# stereo-amp-rev1.net
KiCad netlist of a schematic drawn in EAGLE
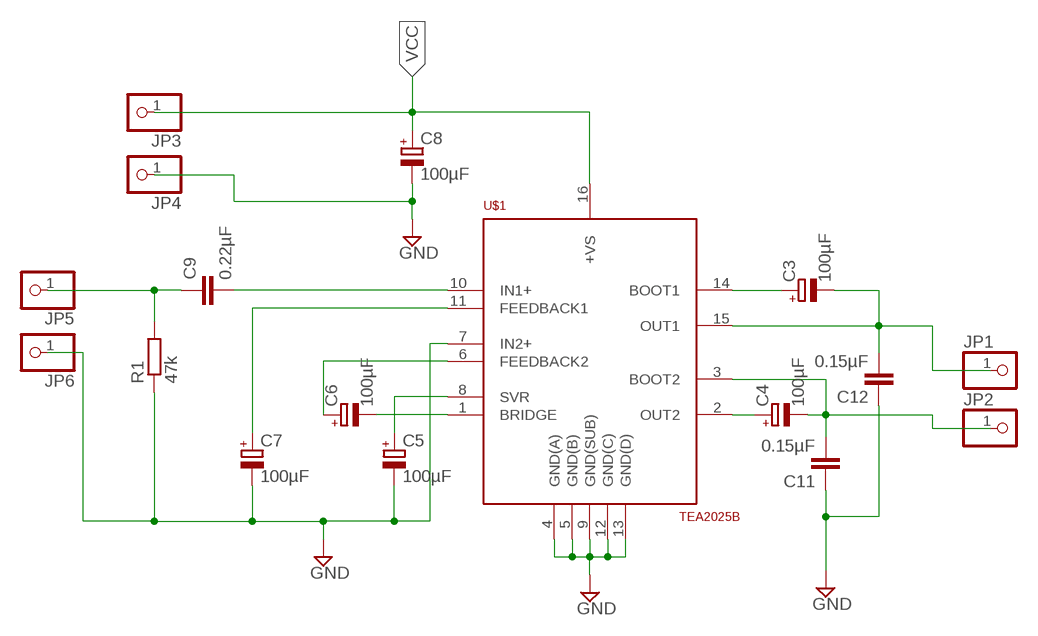
[diagram p0: schematic, sheet 1]

(export (version "E")
  (design (tool "Eeschema 10.0.6"))
  (components
    (comp (ref "C3")
      (value "100µF")
      (footprint "eagle-import:E2,5-7")
      (libsource (lib "eagle-import") (part "CPOL-EUE2.5-7"))
    )
    (comp (ref "C4")
      (value "100µF")
      (footprint "eagle-import:E2,5-7")
      (libsource (lib "eagle-import") (part "CPOL-EUE2.5-7"))
    )
    (comp (ref "C5")
      (value "100µF")
      (footprint "eagle-import:E2,5-7")
      (libsource (lib "eagle-import") (part "CPOL-EUE2.5-7"))
    )
    (comp (ref "C6")
      (value "100µF")
      (footprint "eagle-import:E2,5-7")
      (libsource (lib "eagle-import") (part "CPOL-EUE2.5-7"))
    )
    (comp (ref "C7")
      (value "100µF")
      (footprint "eagle-import:E2,5-7")
      (libsource (lib "eagle-import") (part "CPOL-EUE2.5-7"))
    )
    (comp (ref "C8")
      (value "100µF")
      (footprint "eagle-import:E2,5-7")
      (libsource (lib "eagle-import") (part "CPOL-EUE2.5-7"))
    )
    (comp (ref "C9")
      (value "0.22µF")
      (footprint "eagle-import:C050-024X044")
      (libsource (lib "eagle-import") (part "C-EU050-024X044"))
    )
    (comp (ref "C11")
      (value "0.15µF")
      (footprint "eagle-import:C050-024X044")
      (libsource (lib "eagle-import") (part "C-EU050-024X044"))
    )
    (comp (ref "C12")
      (value "0.15µF")
      (footprint "eagle-import:C050-024X044")
      (libsource (lib "eagle-import") (part "C-EU050-024X044"))
    )
    (comp (ref "JP1")
      (value "PINHD-1X1")
      (footprint "eagle-import:1X01")
      (libsource (lib "eagle-import") (part "PINHD-1X1"))
    )
    (comp (ref "JP2")
      (value "PINHD-1X1")
      (footprint "eagle-import:1X01")
      (libsource (lib "eagle-import") (part "PINHD-1X1"))
    )
    (comp (ref "JP3")
      (value "PINHD-1X1")
      (footprint "eagle-import:1X01")
      (libsource (lib "eagle-import") (part "PINHD-1X1"))
    )
    (comp (ref "JP4")
      (value "PINHD-1X1")
      (footprint "eagle-import:1X01")
      (libsource (lib "eagle-import") (part "PINHD-1X1"))
    )
    (comp (ref "JP5")
      (value "PINHD-1X1")
      (footprint "eagle-import:1X01")
      (libsource (lib "eagle-import") (part "PINHD-1X1"))
    )
    (comp (ref "JP6")
      (value "PINHD-1X1")
      (footprint "eagle-import:1X01")
      (libsource (lib "eagle-import") (part "PINHD-1X1"))
    )
    (comp (ref "R1")
      (value "47k")
      (footprint "eagle-import:0207_10")
      (libsource (lib "eagle-import") (part "R-EU_0207/10"))
    )
    (comp (ref "U$1")
      (value "TEA2025B")
      (footprint "eagle-import:DIL16")
      (libsource (lib "eagle-import") (part "TEA2025B"))
    )
  )
  (nets
    (net (code "1") (name "GND") (class "Default")
      (node (ref "C11") (pin "1") (pinfunction "1_1") (pintype "passive"))
      (node (ref "C12") (pin "1") (pinfunction "1_1") (pintype "passive"))
      (node (ref "C5") (pin "-") (pinfunction "-_-") (pintype "passive"))
      (node (ref "C7") (pin "-") (pinfunction "-_-") (pintype "passive"))
      (node (ref "C8") (pin "-") (pinfunction "-_-") (pintype "passive"))
      (node (ref "JP4") (pin "1") (pinfunction "1_1") (pintype "passive"))
      (node (ref "JP6") (pin "1") (pinfunction "1_1") (pintype "passive"))
      (node (ref "R1") (pin "1") (pinfunction "1_1") (pintype "passive"))
      (node (ref "U$1") (pin "12") (pinfunction "GND(C)_12") (pintype "bidirectional"))
      (node (ref "U$1") (pin "13") (pinfunction "GND(D)_13") (pintype "bidirectional"))
      (node (ref "U$1") (pin "4") (pinfunction "GND(A)_4") (pintype "bidirectional"))
      (node (ref "U$1") (pin "5") (pinfunction "GND(B)_5") (pintype "bidirectional"))
      (node (ref "U$1") (pin "7") (pinfunction "IN2+_7") (pintype "input"))
      (node (ref "U$1") (pin "9") (pinfunction "GND(SUB)_9") (pintype "bidirectional"))
    )
    (net (code "2") (name "Net-(C9-Pad1)") (class "Default")
      (node (ref "C9") (pin "1") (pinfunction "1_1") (pintype "passive"))
      (node (ref "JP5") (pin "1") (pinfunction "1_1") (pintype "passive"))
      (node (ref "R1") (pin "2") (pinfunction "2_2") (pintype "passive"))
    )
    (net (code "3") (name "Net-(U$1-BOOT1)") (class "Default")
      (node (ref "C3") (pin "+") (pinfunction "+_+") (pintype "passive"))
      (node (ref "U$1") (pin "14") (pinfunction "BOOT1_14") (pintype "bidirectional"))
    )
    (net (code "4") (name "Net-(U$1-BOOT2)") (class "Default")
      (node (ref "C11") (pin "2") (pinfunction "2_2") (pintype "passive"))
      (node (ref "C4") (pin "-") (pinfunction "-_-") (pintype "passive"))
      (node (ref "JP2") (pin "1") (pinfunction "1_1") (pintype "passive"))
      (node (ref "U$1") (pin "3") (pinfunction "BOOT2_3") (pintype "bidirectional"))
    )
    (net (code "5") (name "Net-(U$1-BRIDGE)") (class "Default")
      (node (ref "C6") (pin "-") (pinfunction "-_-") (pintype "passive"))
      (node (ref "U$1") (pin "1") (pinfunction "BRIDGE_1") (pintype "bidirectional"))
    )
    (net (code "6") (name "Net-(U$1-FEEDBACK1)") (class "Default")
      (node (ref "C7") (pin "+") (pinfunction "+_+") (pintype "passive"))
      (node (ref "U$1") (pin "11") (pinfunction "FEEDBACK1_11") (pintype "bidirectional"))
    )
    (net (code "7") (name "Net-(U$1-FEEDBACK2)") (class "Default")
      (node (ref "C6") (pin "+") (pinfunction "+_+") (pintype "passive"))
      (node (ref "U$1") (pin "6") (pinfunction "FEEDBACK2_6") (pintype "bidirectional"))
    )
    (net (code "8") (name "Net-(U$1-IN1+)") (class "Default")
      (node (ref "C9") (pin "2") (pinfunction "2_2") (pintype "passive"))
      (node (ref "U$1") (pin "10") (pinfunction "IN1+_10") (pintype "input"))
    )
    (net (code "9") (name "Net-(U$1-OUT1)") (class "Default")
      (node (ref "C12") (pin "2") (pinfunction "2_2") (pintype "passive"))
      (node (ref "C3") (pin "-") (pinfunction "-_-") (pintype "passive"))
      (node (ref "JP1") (pin "1") (pinfunction "1_1") (pintype "passive"))
      (node (ref "U$1") (pin "15") (pinfunction "OUT1_15") (pintype "output"))
    )
    (net (code "10") (name "Net-(U$1-OUT2)") (class "Default")
      (node (ref "C4") (pin "+") (pinfunction "+_+") (pintype "passive"))
      (node (ref "U$1") (pin "2") (pinfunction "OUT2_2") (pintype "output"))
    )
    (net (code "11") (name "Net-(U$1-SVR)") (class "Default")
      (node (ref "C5") (pin "+") (pinfunction "+_+") (pintype "passive"))
      (node (ref "U$1") (pin "8") (pinfunction "SVR_8") (pintype "bidirectional"))
    )
    (net (code "12") (name "VCC") (class "Default")
      (node (ref "C8") (pin "+") (pinfunction "+_+") (pintype "passive"))
      (node (ref "JP3") (pin "1") (pinfunction "1_1") (pintype "passive"))
      (node (ref "U$1") (pin "16") (pinfunction "+VS_16") (pintype "bidirectional"))
    )
  )
)
